# SourceFollower_FET_SOT23.net
KiCad netlist of a schematic drawn in Altium Designer
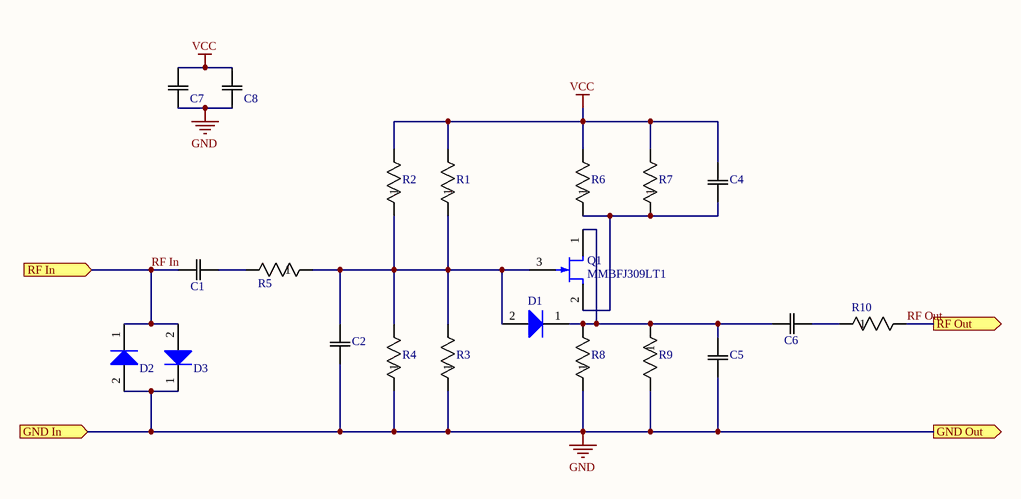
[diagram p0: SourceFollower_FET_SOT23.SchDoc]

(export (version "E")
  (design (tool "Eeschema 10.0.6"))
  (components
    (comp (ref "C1")
      (value "Part Number: C0201C270J3GACTU")
      (footprint "C0201")
      (description "No Description Available")
      (fields
        (field (name "MANUFACTURER_PART_NUMBER") "C0201C270J3GACTU")
        (field (name "COPYRIGHT") "Copyright (C) 2018 Accelerated Designs. All rights reserved")
      )
      (libsource (lib "0201Capacitor_Yageo") (part "C0201C270J3GACTU"))
    )
    (comp (ref "C2")
      (value "Part Number: C0201C270J3GACTU")
      (footprint "C0201")
      (description "No Description Available")
      (fields
        (field (name "MANUFACTURER_PART_NUMBER") "C0201C270J3GACTU")
        (field (name "COPYRIGHT") "Copyright (C) 2018 Accelerated Designs. All rights reserved")
      )
      (libsource (lib "0201Capacitor_Yageo") (part "C0201C270J3GACTU"))
    )
    (comp (ref "C4")
      (value "Part Number: C0201C270J3GACTU")
      (footprint "C0201")
      (description "No Description Available")
      (fields
        (field (name "MANUFACTURER_PART_NUMBER") "C0201C270J3GACTU")
        (field (name "COPYRIGHT") "Copyright (C) 2018 Accelerated Designs. All rights reserved")
      )
      (libsource (lib "0201Capacitor_Yageo") (part "C0201C270J3GACTU"))
    )
    (comp (ref "C5")
      (value "Part Number: C0201C270J3GACTU")
      (footprint "C0201")
      (description "No Description Available")
      (fields
        (field (name "MANUFACTURER_PART_NUMBER") "C0201C270J3GACTU")
        (field (name "COPYRIGHT") "Copyright (C) 2018 Accelerated Designs. All rights reserved")
      )
      (libsource (lib "0201Capacitor_Yageo") (part "C0201C270J3GACTU"))
    )
    (comp (ref "C6")
      (value "Part Number: C0201C270J3GACTU")
      (footprint "C0201")
      (description "No Description Available")
      (fields
        (field (name "MANUFACTURER_PART_NUMBER") "C0201C270J3GACTU")
        (field (name "COPYRIGHT") "Copyright (C) 2018 Accelerated Designs. All rights reserved")
      )
      (libsource (lib "0201Capacitor_Yageo") (part "C0201C270J3GACTU"))
    )
    (comp (ref "C7")
      (value "Part Number: C0201C270J3GACTU")
      (footprint "C0201")
      (description "No Description Available")
      (fields
        (field (name "MANUFACTURER_PART_NUMBER") "C0201C270J3GACTU")
        (field (name "COPYRIGHT") "Copyright (C) 2018 Accelerated Designs. All rights reserved")
      )
      (libsource (lib "0201Capacitor_Yageo") (part "C0201C270J3GACTU"))
    )
    (comp (ref "C8")
      (value "Part Number: C0201C270J3GACTU")
      (footprint "C0201")
      (description "No Description Available")
      (fields
        (field (name "MANUFACTURER_PART_NUMBER") "C0201C270J3GACTU")
        (field (name "COPYRIGHT") "Copyright (C) 2018 Accelerated Designs. All rights reserved")
      )
      (libsource (lib "0201Capacitor_Yageo") (part "C0201C270J3GACTU"))
    )
    (comp (ref "D1")
      (value "BAT15-03W")
      (footprint "INF-SOD323_V")
      (description "Single Silicon Schottky Diode, 110 mA IF Max, SOD32, Green")
      (fields (field (name "MANUFACTURER") "Infineon"))
      (libsource (lib "Infineon_RFSchottkyDiode_SOD323") (part "BAT15-03W"))
    )
    (comp (ref "D2")
      (value "BAT15-03W")
      (footprint "INF-SOD323_V")
      (description "Single Silicon Schottky Diode, 110 mA IF Max, SOD32, Green")
      (fields (field (name "MANUFACTURER") "Infineon"))
      (libsource (lib "Infineon_RFSchottkyDiode_SOD323") (part "BAT15-03W"))
    )
    (comp (ref "D3")
      (value "BAT15-03W")
      (footprint "INF-SOD323_V")
      (description "Single Silicon Schottky Diode, 110 mA IF Max, SOD32, Green")
      (fields (field (name "MANUFACTURER") "Infineon"))
      (libsource (lib "Infineon_RFSchottkyDiode_SOD323") (part "BAT15-03W"))
    )
    (comp (ref "Q1")
      (value "MMBFJ309LT1")
      (footprint "ONSC-SOT-23-3-318-08_V")
      (description "JFET - VHF / UHF Amplifier Transistor, N-Channel, 3-Pin SOT-23, Tape and Reel")
      (fields (field (name "MANUFACTURER") "On Semiconductor"))
      (libsource (lib "ON Semi JFETs") (part "MMBFJ309LT1"))
    )
    (comp (ref "R1")
      (value "Part Number: RC0201FR-0718KL")
      (footprint "RES_RC0201_P6XP3")
      (description "No Description Available")
      (fields
        (field (name "MANUFACTURER_PART_NUMBER") "RC0201FR-0718KL")
        (field (name "COPYRIGHT") "Copyright (C) 2018 Accelerated Designs. All rights reserved")
      )
      (libsource (lib "0201Resistor_Yageo") (part "RC0201FR-0718KL"))
    )
    (comp (ref "R2")
      (value "Part Number: RC0201FR-0718KL")
      (footprint "RES_RC0201_P6XP3")
      (description "No Description Available")
      (fields
        (field (name "MANUFACTURER_PART_NUMBER") "RC0201FR-0718KL")
        (field (name "COPYRIGHT") "Copyright (C) 2018 Accelerated Designs. All rights reserved")
      )
      (libsource (lib "0201Resistor_Yageo") (part "RC0201FR-0718KL"))
    )
    (comp (ref "R3")
      (value "Part Number: RC0201FR-0718KL")
      (footprint "RES_RC0201_P6XP3")
      (description "No Description Available")
      (fields
        (field (name "MANUFACTURER_PART_NUMBER") "RC0201FR-0718KL")
        (field (name "COPYRIGHT") "Copyright (C) 2018 Accelerated Designs. All rights reserved")
      )
      (libsource (lib "0201Resistor_Yageo") (part "RC0201FR-0718KL"))
    )
    (comp (ref "R4")
      (value "Part Number: RC0201FR-0718KL")
      (footprint "RES_RC0201_P6XP3")
      (description "No Description Available")
      (fields
        (field (name "MANUFACTURER_PART_NUMBER") "RC0201FR-0718KL")
        (field (name "COPYRIGHT") "Copyright (C) 2018 Accelerated Designs. All rights reserved")
      )
      (libsource (lib "0201Resistor_Yageo") (part "RC0201FR-0718KL"))
    )
    (comp (ref "R5")
      (value "Part Number: RC0201FR-0718KL")
      (footprint "RES_RC0201_P6XP3")
      (description "No Description Available")
      (fields
        (field (name "MANUFACTURER_PART_NUMBER") "RC0201FR-0718KL")
        (field (name "COPYRIGHT") "Copyright (C) 2018 Accelerated Designs. All rights reserved")
      )
      (libsource (lib "0201Resistor_Yageo") (part "RC0201FR-0718KL"))
    )
    (comp (ref "R6")
      (value "Part Number: RC0201FR-0718KL")
      (footprint "RES_RC0201_P6XP3")
      (description "No Description Available")
      (fields
        (field (name "MANUFACTURER_PART_NUMBER") "RC0201FR-0718KL")
        (field (name "COPYRIGHT") "Copyright (C) 2018 Accelerated Designs. All rights reserved")
      )
      (libsource (lib "0201Resistor_Yageo") (part "RC0201FR-0718KL"))
    )
    (comp (ref "R7")
      (value "Part Number: RC0201FR-0718KL")
      (footprint "RES_RC0201_P6XP3")
      (description "No Description Available")
      (fields
        (field (name "MANUFACTURER_PART_NUMBER") "RC0201FR-0718KL")
        (field (name "COPYRIGHT") "Copyright (C) 2018 Accelerated Designs. All rights reserved")
      )
      (libsource (lib "0201Resistor_Yageo") (part "RC0201FR-0718KL"))
    )
    (comp (ref "R8")
      (value "Part Number: RC0201FR-0718KL")
      (footprint "RES_RC0201_P6XP3")
      (description "No Description Available")
      (fields
        (field (name "MANUFACTURER_PART_NUMBER") "RC0201FR-0718KL")
        (field (name "COPYRIGHT") "Copyright (C) 2018 Accelerated Designs. All rights reserved")
      )
      (libsource (lib "0201Resistor_Yageo") (part "RC0201FR-0718KL"))
    )
    (comp (ref "R9")
      (value "Part Number: RC0201FR-0718KL")
      (footprint "RES_RC0201_P6XP3")
      (description "No Description Available")
      (fields
        (field (name "MANUFACTURER_PART_NUMBER") "RC0201FR-0718KL")
        (field (name "COPYRIGHT") "Copyright (C) 2018 Accelerated Designs. All rights reserved")
      )
      (libsource (lib "0201Resistor_Yageo") (part "RC0201FR-0718KL"))
    )
    (comp (ref "R10")
      (value "Part Number: RC0201FR-0718KL")
      (footprint "RES_RC0201_P6XP3")
      (description "No Description Available")
      (fields
        (field (name "MANUFACTURER_PART_NUMBER") "RC0201FR-0718KL")
        (field (name "COPYRIGHT") "Copyright (C) 2018 Accelerated Designs. All rights reserved")
      )
      (libsource (lib "0201Resistor_Yageo") (part "RC0201FR-0718KL"))
    )
  )
  (nets
    (net (code "1") (name "/RF In") (class "Default")
      (node (ref "C1") (pin "1") (pinfunction "1_1") (pintype "passive"))
      (node (ref "D2") (pin "1") (pinfunction "K_1") (pintype "passive"))
      (node (ref "D3") (pin "2") (pinfunction "A_2") (pintype "passive"))
    )
    (net (code "2") (name "/RF Out") (class "Default")
      (node (ref "R10") (pin "2") (pinfunction "2_2") (pintype "passive"))
    )
    (net (code "3") (name "GND") (class "Default")
      (node (ref "C2") (pin "1") (pinfunction "1_1") (pintype "passive"))
      (node (ref "C5") (pin "1") (pinfunction "1_1") (pintype "passive"))
      (node (ref "C7") (pin "1") (pinfunction "1_1") (pintype "passive"))
      (node (ref "C8") (pin "1") (pinfunction "1_1") (pintype "passive"))
      (node (ref "D2") (pin "2") (pinfunction "A_2") (pintype "passive"))
      (node (ref "D3") (pin "1") (pinfunction "K_1") (pintype "passive"))
      (node (ref "R3") (pin "1") (pinfunction "1_1") (pintype "passive"))
      (node (ref "R4") (pin "1") (pinfunction "1_1") (pintype "passive"))
      (node (ref "R8") (pin "1") (pinfunction "1_1") (pintype "passive"))
      (node (ref "R9") (pin "2") (pinfunction "2_2") (pintype "passive"))
    )
    (net (code "4") (name "Net-(C1-Pad2)") (class "Default")
      (node (ref "C1") (pin "2") (pinfunction "2_2") (pintype "passive"))
      (node (ref "R5") (pin "2") (pinfunction "2_2") (pintype "passive"))
    )
    (net (code "5") (name "Net-(C6-Pad1)") (class "Default")
      (node (ref "C6") (pin "1") (pinfunction "1_1") (pintype "passive"))
      (node (ref "R10") (pin "1") (pinfunction "1_1") (pintype "passive"))
    )
    (net (code "6") (name "Net-(D1-A)") (class "Default")
      (node (ref "C2") (pin "2") (pinfunction "2_2") (pintype "passive"))
      (node (ref "D1") (pin "2") (pinfunction "A_2") (pintype "passive"))
      (node (ref "Q1") (pin "3") (pinfunction "G_3") (pintype "passive"))
      (node (ref "R1") (pin "1") (pinfunction "1_1") (pintype "passive"))
      (node (ref "R2") (pin "1") (pinfunction "1_1") (pintype "passive"))
      (node (ref "R3") (pin "2") (pinfunction "2_2") (pintype "passive"))
      (node (ref "R4") (pin "2") (pinfunction "2_2") (pintype "passive"))
      (node (ref "R5") (pin "1") (pinfunction "1_1") (pintype "passive"))
    )
    (net (code "7") (name "Net-(D1-K)") (class "Default")
      (node (ref "C5") (pin "2") (pinfunction "2_2") (pintype "passive"))
      (node (ref "C6") (pin "2") (pinfunction "2_2") (pintype "passive"))
      (node (ref "D1") (pin "1") (pinfunction "K_1") (pintype "passive"))
      (node (ref "Q1") (pin "1") (pinfunction "D_1") (pintype "passive"))
      (node (ref "R8") (pin "2") (pinfunction "2_2") (pintype "passive"))
      (node (ref "R9") (pin "1") (pinfunction "1_1") (pintype "passive"))
    )
    (net (code "8") (name "Net-(Q1-S)") (class "Default")
      (node (ref "C4") (pin "1") (pinfunction "1_1") (pintype "passive"))
      (node (ref "Q1") (pin "2") (pinfunction "S_2") (pintype "passive"))
      (node (ref "R6") (pin "1") (pinfunction "1_1") (pintype "passive"))
      (node (ref "R7") (pin "1") (pinfunction "1_1") (pintype "passive"))
    )
    (net (code "9") (name "VCC") (class "Default")
      (node (ref "C4") (pin "2") (pinfunction "2_2") (pintype "passive"))
      (node (ref "C7") (pin "2") (pinfunction "2_2") (pintype "passive"))
      (node (ref "C8") (pin "2") (pinfunction "2_2") (pintype "passive"))
      (node (ref "R1") (pin "2") (pinfunction "2_2") (pintype "passive"))
      (node (ref "R2") (pin "2") (pinfunction "2_2") (pintype "passive"))
      (node (ref "R6") (pin "2") (pinfunction "2_2") (pintype "passive"))
      (node (ref "R7") (pin "2") (pinfunction "2_2") (pintype "passive"))
    )
  )
)
